# BSPD.net
KiCad netlist of a schematic drawn in Altium Designer
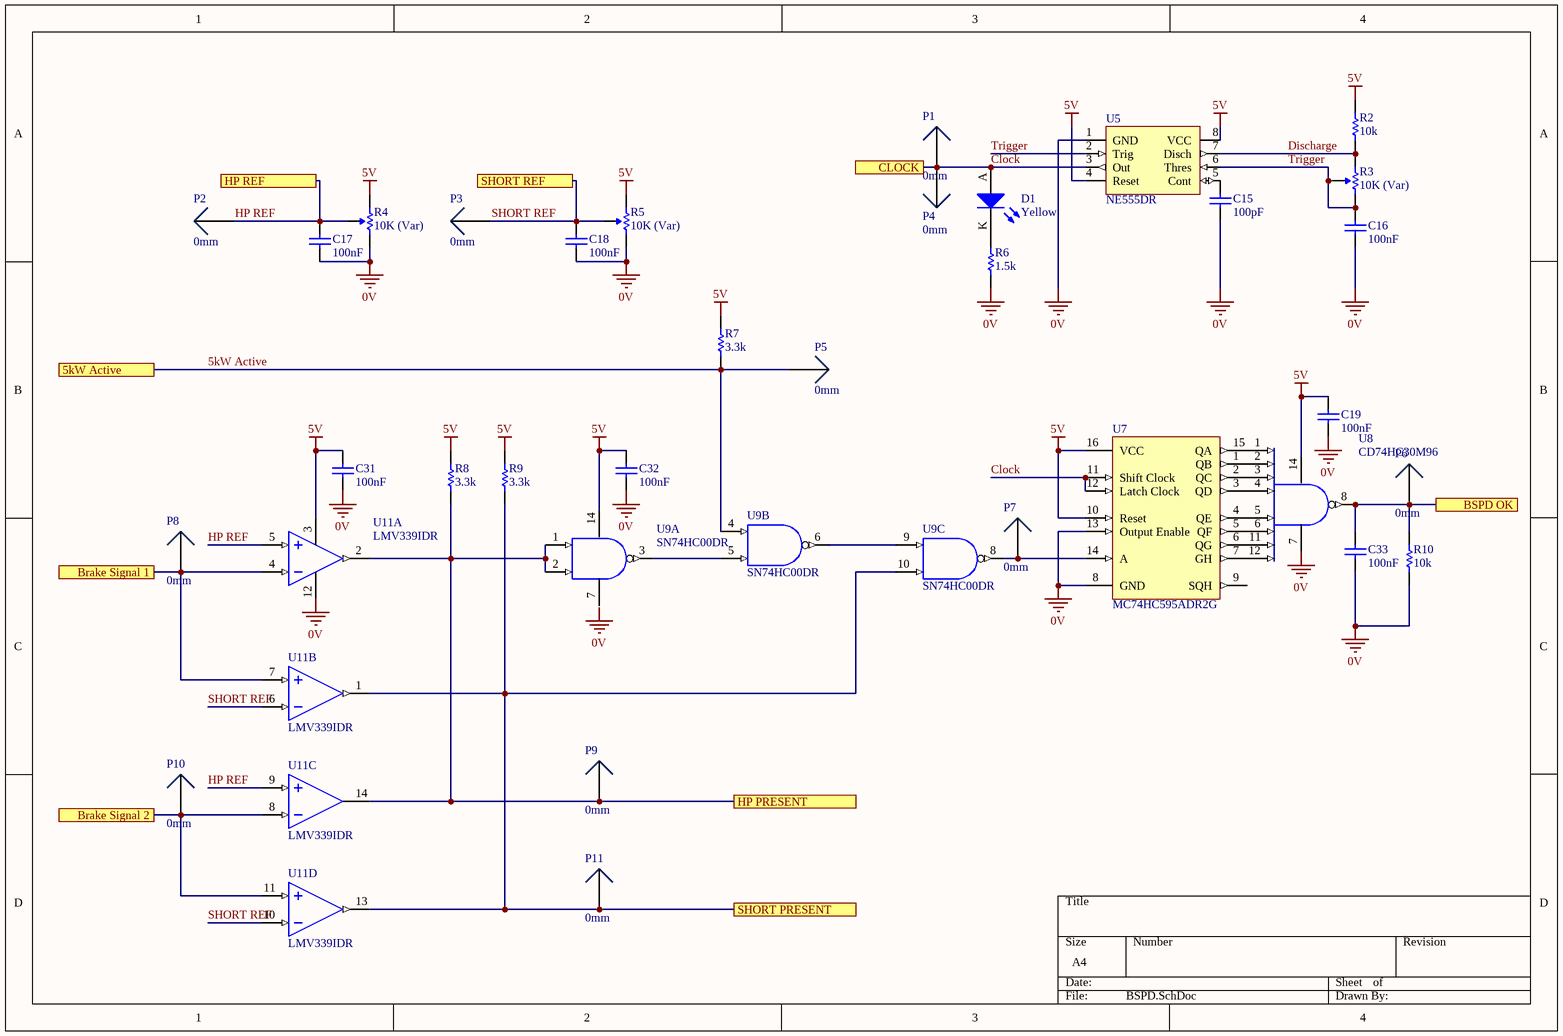
[diagram p0: BSPD.SchDoc]

(export (version "E")
  (design (tool "Eeschema 10.0.6"))
  (components
    (comp (ref "C15")
      (value "100pF")
      (footprint "0805")
      (fields
        (field (name "PART NUMBER") "GCM21B5C1H101JA37L")
        (field (name "TOLERANCE") "5%")
        (field (name "MANUFACTURER") "muRata")
      )
      (libsource (lib "ts_20-standard-library") (part "Capacitor"))
    )
    (comp (ref "C16")
      (value "100nF")
      (footprint "0805")
      (fields
        (field (name "PART NUMBER") "GCM21BR71E104KA37L")
        (field (name "TOLERANCE") "10%")
        (field (name "MANUFACTURER") "muRata")
      )
      (libsource (lib "ts_20-standard-library") (part "Capacitor"))
    )
    (comp (ref "C17")
      (value "100nF")
      (footprint "0805")
      (fields
        (field (name "PART NUMBER") "GCM21BR71E104KA37L")
        (field (name "TOLERANCE") "10%")
        (field (name "MANUFACTURER") "muRata")
      )
      (libsource (lib "ts_20-standard-library") (part "Capacitor"))
    )
    (comp (ref "C18")
      (value "100nF")
      (footprint "0805")
      (fields
        (field (name "PART NUMBER") "GCM21BR71E104KA37L")
        (field (name "TOLERANCE") "10%")
        (field (name "MANUFACTURER") "muRata")
      )
      (libsource (lib "ts_20-standard-library") (part "Capacitor"))
    )
    (comp (ref "C19")
      (value "100nF")
      (footprint "0805")
      (fields
        (field (name "PART NUMBER") "GCM21BR71E104KA37L")
        (field (name "TOLERANCE") "10%")
        (field (name "MANUFACTURER") "muRata")
      )
      (libsource (lib "ts_20-standard-library") (part "Capacitor"))
    )
    (comp (ref "C31")
      (value "100nF")
      (footprint "0805")
      (fields
        (field (name "PART NUMBER") "GCM21BR71E104KA37L")
        (field (name "TOLERANCE") "10%")
        (field (name "MANUFACTURER") "muRata")
      )
      (libsource (lib "ts_20-standard-library") (part "Capacitor"))
    )
    (comp (ref "C32")
      (value "100nF")
      (footprint "0805")
      (fields
        (field (name "PART NUMBER") "GCM21BR71E104KA37L")
        (field (name "TOLERANCE") "10%")
        (field (name "MANUFACTURER") "muRata")
      )
      (libsource (lib "ts_20-standard-library") (part "Capacitor"))
    )
    (comp (ref "C33")
      (value "100nF")
      (footprint "0805")
      (fields
        (field (name "PART NUMBER") "GCM21BR71E104KA37L")
        (field (name "TOLERANCE") "10%")
        (field (name "MANUFACTURER") "muRata")
      )
      (libsource (lib "ts_20-standard-library") (part "Capacitor"))
    )
    (comp (ref "D1")
      (value "Yellow")
      (footprint "0805 LED")
      (description "Yellow LED Indication - Discrete 1.75V 0805 (2012 Metric)")
      (fields (field (name "PART NUMBER") "SML-211YTT86") (field (name "MANUFACTURER") "ROHM Semiconductor"))
      (libsource (lib "ts_20-standard-library") (part "LED"))
    )
    (comp (ref "P1")
      (value "0mm")
      (footprint "SMD Test Point")
      (fields (field (name "PART NUMBER") "SMD Test Point") (field (name "CONTACT") "NA"))
      (libsource (lib "ts_20-standard-connectors") (part "Test Point"))
    )
    (comp (ref "P2")
      (value "0mm")
      (footprint "TH Test Point")
      (fields (field (name "PART NUMBER") "TH Test Point") (field (name "CONTACT") "NA"))
      (libsource (lib "ts_20-standard-connectors") (part "Test Point"))
    )
    (comp (ref "P3")
      (value "0mm")
      (footprint "TH Test Point")
      (fields (field (name "PART NUMBER") "TH Test Point") (field (name "CONTACT") "NA"))
      (libsource (lib "ts_20-standard-connectors") (part "Test Point"))
    )
    (comp (ref "P4")
      (value "0mm")
      (footprint "TH Test Point")
      (fields (field (name "PART NUMBER") "TH Test Point") (field (name "CONTACT") "NA"))
      (libsource (lib "ts_20-standard-connectors") (part "Test Point"))
    )
    (comp (ref "P5")
      (value "0mm")
      (footprint "SMD Test Point")
      (fields (field (name "PART NUMBER") "SMD Test Point") (field (name "CONTACT") "NA"))
      (libsource (lib "ts_20-standard-connectors") (part "Test Point"))
    )
    (comp (ref "P6")
      (value "0mm")
      (footprint "SMD Test Point")
      (fields (field (name "PART NUMBER") "SMD Test Point") (field (name "CONTACT") "NA"))
      (libsource (lib "ts_20-standard-connectors") (part "Test Point"))
    )
    (comp (ref "P7")
      (value "0mm")
      (footprint "SMD Test Point")
      (fields (field (name "PART NUMBER") "SMD Test Point") (field (name "CONTACT") "NA"))
      (libsource (lib "ts_20-standard-connectors") (part "Test Point"))
    )
    (comp (ref "P8")
      (value "0mm")
      (footprint "TH Test Point")
      (fields (field (name "PART NUMBER") "TH Test Point") (field (name "CONTACT") "NA"))
      (libsource (lib "ts_20-standard-connectors") (part "Test Point"))
    )
    (comp (ref "P9")
      (value "0mm")
      (footprint "SMD Test Point")
      (fields (field (name "PART NUMBER") "SMD Test Point") (field (name "CONTACT") "NA"))
      (libsource (lib "ts_20-standard-connectors") (part "Test Point"))
    )
    (comp (ref "P10")
      (value "0mm")
      (footprint "TH Test Point")
      (fields (field (name "PART NUMBER") "TH Test Point") (field (name "CONTACT") "NA"))
      (libsource (lib "ts_20-standard-connectors") (part "Test Point"))
    )
    (comp (ref "P11")
      (value "0mm")
      (footprint "SMD Test Point")
      (fields (field (name "PART NUMBER") "SMD Test Point") (field (name "CONTACT") "NA"))
      (libsource (lib "ts_20-standard-connectors") (part "Test Point"))
    )
    (comp (ref "R2")
      (value "10k")
      (footprint "0805")
      (fields
        (field (name "PART NUMBER") "RC0805FR0710KL")
        (field (name "MANUFACTURER") "YAGEO")
        (field (name "TOLERANCE") "0.01")
      )
      (libsource (lib "ts_20-standard-library") (part "Resistor"))
    )
    (comp (ref "R3")
      (value "10K (Var)")
      (footprint "B 3296")
      (fields
        (field (name "PART NUMBER") "3296W-1-103LF")
        (field (name "MANUFACTURER") "Bournes Inc")
        (field (name "TOLERANCE") "0.1")
      )
      (libsource (lib "ts_20-standard-library") (part "Resistor (Potentiometer)"))
    )
    (comp (ref "R4")
      (value "10K (Var)")
      (footprint "B 3296")
      (fields
        (field (name "PART NUMBER") "3296W-1-103LF")
        (field (name "MANUFACTURER") "Bournes Inc")
        (field (name "TOLERANCE") "0.1")
      )
      (libsource (lib "ts_20-standard-library") (part "Resistor (Potentiometer)"))
    )
    (comp (ref "R5")
      (value "10K (Var)")
      (footprint "B 3296")
      (fields
        (field (name "PART NUMBER") "3296W-1-103LF")
        (field (name "MANUFACTURER") "Bournes Inc")
        (field (name "TOLERANCE") "0.1")
      )
      (libsource (lib "ts_20-standard-library") (part "Resistor (Potentiometer)"))
    )
    (comp (ref "R6")
      (value "1.5k")
      (footprint "0805")
      (fields
        (field (name "PART NUMBER") "RC0805FR071K5L")
        (field (name "MANUFACTURER") "YAGEO")
        (field (name "TOLERANCE") "0.01")
      )
      (libsource (lib "ts_20-standard-library") (part "Resistor"))
    )
    (comp (ref "R7")
      (value "3.3k")
      (footprint "0805")
      (fields
        (field (name "PART NUMBER") "RC0805FR073K3L")
        (field (name "MANUFACTURER") "YAGEO")
        (field (name "TOLERANCE") "0.01")
      )
      (libsource (lib "ts_20-standard-library") (part "Resistor"))
    )
    (comp (ref "R8")
      (value "3.3k")
      (footprint "0805")
      (fields
        (field (name "PART NUMBER") "RC0805FR073K3L")
        (field (name "MANUFACTURER") "YAGEO")
        (field (name "TOLERANCE") "0.01")
      )
      (libsource (lib "ts_20-standard-library") (part "Resistor"))
    )
    (comp (ref "R9")
      (value "3.3k")
      (footprint "0805")
      (fields
        (field (name "PART NUMBER") "RC0805FR073K3L")
        (field (name "MANUFACTURER") "YAGEO")
        (field (name "TOLERANCE") "0.01")
      )
      (libsource (lib "ts_20-standard-library") (part "Resistor"))
    )
    (comp (ref "R10")
      (value "10k")
      (footprint "0805")
      (fields
        (field (name "PART NUMBER") "RC0805FR0710KL")
        (field (name "MANUFACTURER") "YAGEO")
        (field (name "TOLERANCE") "0.01")
      )
      (libsource (lib "ts_20-standard-library") (part "Resistor"))
    )
    (comp (ref "U5")
      (value "NE555DR")
      (footprint "TI 8-SOIC")
      (description "IC OSC SGL TIMER 100KHZ 8-SOIC")
      (fields
        (field (name "MANUFACTURER") "Texas Instruments")
        (field (name "DIGIKEY PART NUMBER") "296-6501-1-ND")
      )
      (libsource (lib "ts_20-standard-library") (part "NE555DR"))
    )
    (comp (ref "U7")
      (value "MC74HC595ADR2G")
      (footprint "ON 16-SOIC")
      (description "IC SHIFT REGISTR 8BIT 3ST 16SOIC")
      (fields
        (field (name "MANUFACTURER") "ON Semiconductor")
        (field (name "DIGIKEY PART NUMBER") "MC74HC595ADR2GOSCT-ND")
      )
      (libsource (lib "ts_20-standard-library") (part "MC74HC595ADR2G"))
    )
    (comp (ref "U8")
      (value "CD74HC30M96")
      (footprint "TI 14-SOIC")
      (description "IC GATE NAND 1CH 8-INP 14SOIC")
      (fields
        (field (name "MANUFACTURER") "Texas Instruments")
        (field (name "DIGIKEY PART NUMBER") "296-14521-1-ND")
      )
      (libsource (lib "ts_20-standard-library") (part "CD74HC30M96"))
    )
    (comp (ref "U9")
      (value "SN74HC00DR")
      (footprint "TI 14-SOIC")
      (description "NAND Gate IC 4 Channel 14-SOIC")
      (fields
        (field (name "MANUFACTURER") "Texas Instruments")
        (field (name "DIGIKEY PART NUMBER") "296-1187-2-ND")
      )
      (libsource (lib "ts_20-standard-library") (part "SN74HC00DR"))
    )
    (comp (ref "U11")
      (value "LMV339IDR")
      (footprint "TI 14-SOIC")
      (description "Comparator General Purpose Open Collector 14-SOIC")
      (fields
        (field (name "MANUFACTURER") "Texas Instruments")
        (field (name "DIGIKEY PART NUMBER") "296-6611-2-ND")
      )
      (libsource (lib "ts_20-standard-library") (part "LMV339IDR"))
    )
  )
  (nets
    (net (code "1") (name "/5kW Active") (class "Default")
      (node (ref "P5") (pin "1") (pinfunction "1_1") (pintype "passive"))
      (node (ref "R7") (pin "1") (pinfunction "1_1") (pintype "passive"))
      (node (ref "U9") (pin "4") (pinfunction "2A_4") (pintype "input"))
    )
    (net (code "2") (name "/BSPD OK") (class "Default")
      (node (ref "C33") (pin "2") (pinfunction "2_2") (pintype "passive"))
      (node (ref "P6") (pin "1") (pinfunction "1_1") (pintype "passive"))
      (node (ref "R10") (pin "2") (pinfunction "2_2") (pintype "passive"))
      (node (ref "U8") (pin "8") (pinfunction "Output_8") (pintype "output"))
    )
    (net (code "3") (name "/Brake Signal 1") (class "Default")
      (node (ref "P8") (pin "1") (pinfunction "1_1") (pintype "passive"))
      (node (ref "U11") (pin "4") (pinfunction "IN_A-_4") (pintype "input"))
      (node (ref "U11") (pin "7") (pinfunction "IN_B+_7") (pintype "input"))
    )
    (net (code "4") (name "/Brake Signal 2") (class "Default")
      (node (ref "P10") (pin "1") (pinfunction "1_1") (pintype "passive"))
      (node (ref "U11") (pin "11") (pinfunction "IN_D+_11") (pintype "input"))
      (node (ref "U11") (pin "8") (pinfunction "IN_C-_8") (pintype "input"))
    )
    (net (code "5") (name "/Clock") (class "Default")
      (node (ref "D1") (pin "A") (pinfunction "A_A") (pintype "passive"))
      (node (ref "P1") (pin "1") (pinfunction "1_1") (pintype "passive"))
      (node (ref "P4") (pin "1") (pinfunction "1_1") (pintype "passive"))
      (node (ref "U5") (pin "3") (pinfunction "Out_3") (pintype "output"))
      (node (ref "U7") (pin "11") (pinfunction "Shift_Clock_11") (pintype "input"))
      (node (ref "U7") (pin "12") (pinfunction "Latch_Clock_12") (pintype "input"))
    )
    (net (code "6") (name "/Discharge") (class "Default")
      (node (ref "R2") (pin "1") (pinfunction "1_1") (pintype "passive"))
      (node (ref "R3") (pin "3") (pinfunction "CW_3") (pintype "passive"))
      (node (ref "U5") (pin "7") (pinfunction "Disch_7") (pintype "output"))
    )
    (net (code "7") (name "/HP PRESENT") (class "Default")
      (node (ref "P9") (pin "1") (pinfunction "1_1") (pintype "passive"))
      (node (ref "R8") (pin "1") (pinfunction "1_1") (pintype "passive"))
      (node (ref "U11") (pin "14") (pinfunction "OUT_C_14") (pintype "passive"))
      (node (ref "U11") (pin "2") (pinfunction "OUT_A_2") (pintype "output"))
      (node (ref "U9") (pin "1") (pinfunction "1A_1") (pintype "input"))
      (node (ref "U9") (pin "2") (pinfunction "1B_2") (pintype "input"))
    )
    (net (code "8") (name "/HP REF") (class "Default")
      (node (ref "C17") (pin "2") (pinfunction "2_2") (pintype "passive"))
      (node (ref "P2") (pin "1") (pinfunction "1_1") (pintype "passive"))
      (node (ref "R4") (pin "2") (pinfunction "Wiper_2") (pintype "passive"))
      (node (ref "U11") (pin "5") (pinfunction "IN_A+_5") (pintype "input"))
      (node (ref "U11") (pin "9") (pinfunction "IN_C+_9") (pintype "input"))
    )
    (net (code "9") (name "/SHORT PRESENT") (class "Default")
      (node (ref "P11") (pin "1") (pinfunction "1_1") (pintype "passive"))
      (node (ref "R9") (pin "1") (pinfunction "1_1") (pintype "passive"))
      (node (ref "U11") (pin "1") (pinfunction "OUT_B_1") (pintype "output"))
      (node (ref "U11") (pin "13") (pinfunction "OUT_D_13") (pintype "output"))
      (node (ref "U9") (pin "10") (pinfunction "3B_10") (pintype "input"))
    )
    (net (code "10") (name "/SHORT REF") (class "Default")
      (node (ref "C18") (pin "2") (pinfunction "2_2") (pintype "passive"))
      (node (ref "P3") (pin "1") (pinfunction "1_1") (pintype "passive"))
      (node (ref "R5") (pin "2") (pinfunction "Wiper_2") (pintype "passive"))
      (node (ref "U11") (pin "10") (pinfunction "IN_D-_10") (pintype "input"))
      (node (ref "U11") (pin "6") (pinfunction "IN_B-_6") (pintype "input"))
    )
    (net (code "11") (name "/Trigger") (class "Default")
      (node (ref "C16") (pin "2") (pinfunction "2_2") (pintype "passive"))
      (node (ref "R3") (pin "1") (pinfunction "CCW_1") (pintype "passive"))
      (node (ref "R3") (pin "2") (pinfunction "Wiper_2") (pintype "passive"))
      (node (ref "U5") (pin "2") (pinfunction "Trig_2") (pintype "input"))
      (node (ref "U5") (pin "6") (pinfunction "Thres_6") (pintype "input"))
    )
    (net (code "12") (name "0V") (class "Default")
      (node (ref "C15") (pin "1") (pinfunction "1_1") (pintype "passive"))
      (node (ref "C16") (pin "1") (pinfunction "1_1") (pintype "passive"))
      (node (ref "C17") (pin "1") (pinfunction "1_1") (pintype "passive"))
      (node (ref "C18") (pin "1") (pinfunction "1_1") (pintype "passive"))
      (node (ref "C19") (pin "1") (pinfunction "1_1") (pintype "passive"))
      (node (ref "C31") (pin "1") (pinfunction "1_1") (pintype "passive"))
      (node (ref "C32") (pin "1") (pinfunction "1_1") (pintype "passive"))
      (node (ref "C33") (pin "1") (pinfunction "1_1") (pintype "passive"))
      (node (ref "R10") (pin "1") (pinfunction "1_1") (pintype "passive"))
      (node (ref "R4") (pin "1") (pinfunction "CCW_1") (pintype "passive"))
      (node (ref "R5") (pin "1") (pinfunction "CCW_1") (pintype "passive"))
      (node (ref "R6") (pin "1") (pinfunction "1_1") (pintype "passive"))
      (node (ref "U11") (pin "12") (pinfunction "V-_12") (pintype "power_in"))
      (node (ref "U5") (pin "1") (pinfunction "GND_1") (pintype "power_in"))
      (node (ref "U7") (pin "13") (pinfunction "Output_Enable_13") (pintype "input"))
      (node (ref "U7") (pin "8") (pinfunction "GND_8") (pintype "power_in"))
      (node (ref "U8") (pin "7") (pinfunction "GND_7") (pintype "power_in"))
    )
    (net (code "13") (name "5V") (class "Default")
      (node (ref "C19") (pin "2") (pinfunction "2_2") (pintype "passive"))
      (node (ref "C31") (pin "2") (pinfunction "2_2") (pintype "passive"))
      (node (ref "C32") (pin "2") (pinfunction "2_2") (pintype "passive"))
      (node (ref "R2") (pin "2") (pinfunction "2_2") (pintype "passive"))
      (node (ref "R4") (pin "3") (pinfunction "CW_3") (pintype "passive"))
      (node (ref "R5") (pin "3") (pinfunction "CW_3") (pintype "passive"))
      (node (ref "R7") (pin "2") (pinfunction "2_2") (pintype "passive"))
      (node (ref "R8") (pin "2") (pinfunction "2_2") (pintype "passive"))
      (node (ref "R9") (pin "2") (pinfunction "2_2") (pintype "passive"))
      (node (ref "U11") (pin "3") (pinfunction "V+_3") (pintype "power_in"))
      (node (ref "U5") (pin "4") (pinfunction "Reset_4") (pintype "passive"))
      (node (ref "U5") (pin "8") (pinfunction "VCC_8") (pintype "passive"))
      (node (ref "U7") (pin "10") (pinfunction "Reset_10") (pintype "input"))
      (node (ref "U7") (pin "16") (pinfunction "VCC_16") (pintype "power_in"))
      (node (ref "U8") (pin "14") (pinfunction "VCC_14") (pintype "power_in"))
      (node (ref "U9") (pin "14") (pinfunction "VCC_14") (pintype "power_in"))
    )
    (net (code "14") (name "Net-(D1-PadK)") (class "Default")
      (node (ref "D1") (pin "K") (pinfunction "K_K") (pintype "passive"))
      (node (ref "R6") (pin "2") (pinfunction "2_2") (pintype "passive"))
    )
    (net (code "15") (name "Net-(U5-Cont)") (class "Default")
      (node (ref "C15") (pin "2") (pinfunction "2_2") (pintype "passive"))
      (node (ref "U5") (pin "5") (pinfunction "Cont_5") (pintype "bidirectional"))
    )
    (net (code "16") (name "Net-(U7-A)") (class "Default")
      (node (ref "P7") (pin "1") (pinfunction "1_1") (pintype "passive"))
      (node (ref "U7") (pin "14") (pinfunction "A_14") (pintype "input"))
      (node (ref "U9") (pin "8") (pinfunction "3Y_8") (pintype "output"))
    )
    (net (code "17") (name "Net-(U7-GH)") (class "Default")
      (node (ref "U7") (pin "7") (pinfunction "GH_7") (pintype "output"))
      (node (ref "U8") (pin "12") (pinfunction "Input_12") (pintype "input"))
    )
    (net (code "18") (name "Net-(U7-QA)") (class "Default")
      (node (ref "U7") (pin "15") (pinfunction "QA_15") (pintype "output"))
      (node (ref "U8") (pin "1") (pinfunction "Input_1") (pintype "input"))
    )
    (net (code "19") (name "Net-(U7-QB)") (class "Default")
      (node (ref "U7") (pin "1") (pinfunction "QB_1") (pintype "output"))
      (node (ref "U8") (pin "2") (pinfunction "Input_2") (pintype "input"))
    )
    (net (code "20") (name "Net-(U7-QC)") (class "Default")
      (node (ref "U7") (pin "2") (pinfunction "QC_2") (pintype "output"))
      (node (ref "U8") (pin "3") (pinfunction "Input_3") (pintype "input"))
    )
    (net (code "21") (name "Net-(U7-QD)") (class "Default")
      (node (ref "U7") (pin "3") (pinfunction "QD_3") (pintype "output"))
      (node (ref "U8") (pin "4") (pinfunction "Input_4") (pintype "input"))
    )
    (net (code "22") (name "Net-(U7-QE)") (class "Default")
      (node (ref "U7") (pin "4") (pinfunction "QE_4") (pintype "output"))
      (node (ref "U8") (pin "5") (pinfunction "Input_5") (pintype "input"))
    )
    (net (code "23") (name "Net-(U7-QF)") (class "Default")
      (node (ref "U7") (pin "5") (pinfunction "QF_5") (pintype "output"))
      (node (ref "U8") (pin "6") (pinfunction "Input_6") (pintype "input"))
    )
    (net (code "24") (name "Net-(U7-QG)") (class "Default")
      (node (ref "U7") (pin "6") (pinfunction "QG_6") (pintype "output"))
      (node (ref "U8") (pin "11") (pinfunction "Input_11") (pintype "input"))
    )
    (net (code "25") (name "Net-(U9A-1Y)") (class "Default")
      (node (ref "U9") (pin "3") (pinfunction "1Y_3") (pintype "output"))
      (node (ref "U9") (pin "5") (pinfunction "2B_5") (pintype "input"))
    )
    (net (code "26") (name "Net-(U9B-2Y)") (class "Default")
      (node (ref "U9") (pin "6") (pinfunction "2Y_6") (pintype "output"))
      (node (ref "U9") (pin "9") (pinfunction "3A_9") (pintype "input"))
    )
    (net (code "27") (name "unconnected-(U7-SQH-Pad9)") (class "Default")
      (node (ref "U7") (pin "9") (pinfunction "SQH_9") (pintype "output"))
    )
    (net (code "28") (name "unconnected-(U9A-GND-Pad7)") (class "Default")
      (node (ref "U9") (pin "7") (pinfunction "GND_7") (pintype "power_in"))
    )
  )
)
